# ADC.net
KiCad netlist of a schematic drawn in Altium Designer
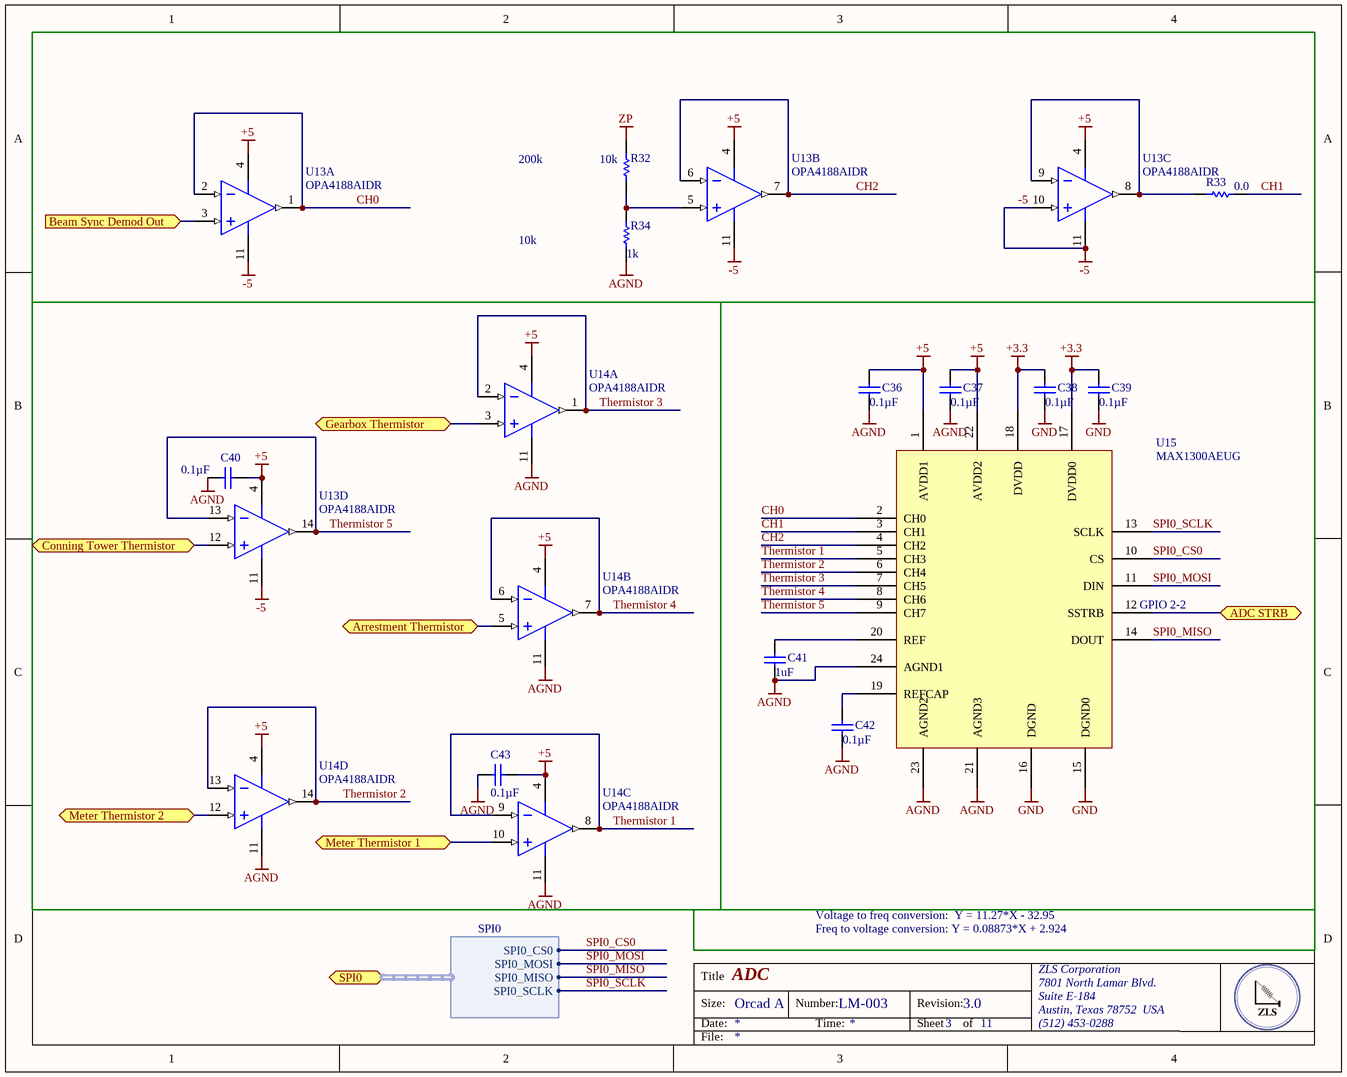
[diagram p0: ADC.SchDoc]

(export (version "E")
  (design (tool "Eeschema 10.0.6"))
  (components
    (comp (ref "C36")
      (value "CAP CER 0.1UF 25V X7R 0805")
      (footprint "CAPC0805(2012)145_N")
      (fields
        (field (name "MANUFACTURER") "Murata Electronics North America")
        (field (name "MANUFACTURER PART NUMBER") "GRM21BR71E104KA01L")
        (field (name "CAPACITANCE") "0.1µF")
        (field (name "TOLERANCE") "±10%")
      )
      (libsource (lib "Altium Content Vault") (part "CMP-1036-04795-1"))
    )
    (comp (ref "C37")
      (value "CAP CER 0.1UF 25V X7R 0805")
      (footprint "CAPC0805(2012)145_N")
      (fields
        (field (name "MANUFACTURER") "Murata Electronics North America")
        (field (name "MANUFACTURER PART NUMBER") "GRM21BR71E104KA01L")
        (field (name "CAPACITANCE") "0.1µF")
        (field (name "TOLERANCE") "±10%")
      )
      (libsource (lib "Altium Content Vault") (part "CMP-1036-04795-1"))
    )
    (comp (ref "C38")
      (value "CAP CER 0.1UF 25V X7R 0805")
      (footprint "CAPC0805(2012)145_N")
      (fields
        (field (name "MANUFACTURER") "Murata Electronics North America")
        (field (name "MANUFACTURER PART NUMBER") "GRM21BR71E104KA01L")
        (field (name "CAPACITANCE") "0.1µF")
        (field (name "TOLERANCE") "±10%")
      )
      (libsource (lib "Altium Content Vault") (part "CMP-1036-04795-1"))
    )
    (comp (ref "C39")
      (value "CAP CER 0.1UF 25V X7R 0805")
      (footprint "CAPC0805(2012)145_N")
      (fields
        (field (name "MANUFACTURER") "Murata Electronics North America")
        (field (name "MANUFACTURER PART NUMBER") "GRM21BR71E104KA01L")
        (field (name "CAPACITANCE") "0.1µF")
        (field (name "TOLERANCE") "±10%")
      )
      (libsource (lib "Altium Content Vault") (part "CMP-1036-04795-1"))
    )
    (comp (ref "C40")
      (value "CAP CER 0.1UF 16V X7R 0805")
      (footprint "CAPC0805(2012)145_N")
      (fields
        (field (name "TOLERANCE") "±10%")
        (field (name "MANUFACTURER") "Murata Electronics North America")
        (field (name "MANUFACTURER PART NUMBER") "GRM219R71C104KA01D")
        (field (name "CAPACITANCE") "0.1µF")
      )
      (libsource (lib "Altium Content Vault") (part "CMP-1036-04795-1"))
    )
    (comp (ref "C41")
      (value "CAP CER 1UF 16V X7R 0805")
      (footprint "CAPC0805(2012)145_N")
      (fields
        (field (name "MANUFACTURER") "Kemet")
        (field (name "MANUFACTURER PART NUMBER") "C0805X105K4RACTU")
        (field (name "CAPACITANCE") "1uF")
        (field (name "TOLERANCE") "10%")
      )
      (libsource (lib "Altium Content Vault") (part "CMP-1036-04795-1"))
    )
    (comp (ref "C42")
      (value "CAP CER 0.1UF 16V X7R 0805")
      (footprint "CAPC0805(2012)145_N")
      (fields
        (field (name "TOLERANCE") "±10%")
        (field (name "MANUFACTURER") "Murata Electronics North America")
        (field (name "MANUFACTURER PART NUMBER") "GRM219R71C104KA01D")
        (field (name "CAPACITANCE") "0.1µF")
      )
      (libsource (lib "Altium Content Vault") (part "CMP-1036-04795-1"))
    )
    (comp (ref "C43")
      (value "CAP CER 0.1UF 16V X7R 0805")
      (footprint "CAPC0805(2012)145_N")
      (fields
        (field (name "TOLERANCE") "±10%")
        (field (name "MANUFACTURER") "Murata Electronics North America")
        (field (name "MANUFACTURER PART NUMBER") "GRM219R71C104KA01D")
        (field (name "CAPACITANCE") "0.1µF")
      )
      (libsource (lib "Altium Content Vault") (part "CMP-1036-04795-1"))
    )
    (comp (ref "R32")
      (value "RES SMD 10K OHM 1% 1/8W 0805")
      (footprint "RESC0805(2012)_M")
      (fields
        (field (name "MANUFACTURER") "Vishay Dale")
        (field (name "MANUFACTURER PART NUMBER") "CRCW080510K0FKTA")
        (field (name "RESISTANCE (OHMS)") "10k")
        (field (name "TOLERANCE") "±1%")
      )
      (libsource (lib "Altium Content Vault") (part "CMP-1013-00017-1"))
    )
    (comp (ref "R33")
      (value "RES SMD 0.0 OHM JUMPER 1/8W 0805")
      (footprint "RESC0805(2012)_M")
      (fields
        (field (name "MANUFACTURER") "Vishay Dale")
        (field (name "MANUFACTURER PART NUMBER") "CRCW08050000Z0EA")
        (field (name "RESISTANCE (OHMS)") "0.0")
        (field (name "TOLERANCE") "Jumper")
      )
      (libsource (lib "Altium Content Vault") (part "CMP-1013-00017-1"))
    )
    (comp (ref "R34")
      (value "RES SMD 1K OHM 1% 1/8W 0805")
      (footprint "RESC0805(2012)_M")
      (fields
        (field (name "MANUFACTURER") "Vishay Dale")
        (field (name "MANUFACTURER PART NUMBER") "CRCW08051K00FKTA")
        (field (name "RESISTANCE (OHMS)") "1k")
        (field (name "TOLERANCE") "±1%")
      )
      (libsource (lib "Altium Content Vault") (part "CMP-1013-00017-1"))
    )
    (comp (ref "U13")
      (value "OPA4188AIDR")
      (footprint "D0014A_L")
      (fields (field (name "MANUFACTURER") "Texas Instruments"))
      (libsource (lib "Altium Content Vault") (part "TI-OPA4188-D14"))
    )
    (comp (ref "U14")
      (value "OPA4188AIDR")
      (footprint "D0014A_L")
      (fields (field (name "MANUFACTURER") "Texas Instruments"))
      (libsource (lib "Altium Content Vault") (part "TI-OPA4188-D14"))
    )
    (comp (ref "U15")
      (value "MAX1300AEUG")
      (footprint "TSOP65P640X90-24N")
      (description "IC ADC 16BIT SRL 115KSPS 24TSSOP")
      (libsource (lib "ZLS_LIB") (part "MAX1300AEUG"))
    )
  )
  (nets
    (net (code "2") (name "+3.3") (class "Default")
      (node (ref "C38") (pin "1") (pinfunction "1_1") (pintype "passive"))
      (node (ref "C39") (pin "1") (pinfunction "1_1") (pintype "passive"))
      (node (ref "U15") (pin "17") (pinfunction "DVDD0_17") (pintype "passive"))
      (node (ref "U15") (pin "18") (pinfunction "DVDD_18") (pintype "passive"))
    )
    (net (code "3") (name "+5") (class "Default")
      (node (ref "C36") (pin "1") (pinfunction "1_1") (pintype "passive"))
      (node (ref "C37") (pin "1") (pinfunction "1_1") (pintype "passive"))
      (node (ref "C40") (pin "2") (pinfunction "2_2") (pintype "passive"))
      (node (ref "C43") (pin "2") (pinfunction "2_2") (pintype "passive"))
      (node (ref "U13") (pin "4") (pinfunction "V+_4") (pintype "power_in"))
      (node (ref "U14") (pin "4") (pinfunction "V+_4") (pintype "power_in"))
      (node (ref "U15") (pin "1") (pinfunction "AVDD1_1") (pintype "passive"))
      (node (ref "U15") (pin "22") (pinfunction "AVDD2_22") (pintype "passive"))
    )
    (net (code "4") (name "-5") (class "Default")
      (node (ref "U13") (pin "10") (pinfunction "IN_C+_10") (pintype "input"))
      (node (ref "U13") (pin "11") (pinfunction "V-_11") (pintype "power_in"))
    )
    (net (code "5") (name "/ADC STRB") (class "Default")
      (node (ref "U15") (pin "12") (pinfunction "SSTRB_12") (pintype "passive"))
    )
    (net (code "6") (name "/Arrestment Thermistor") (class "Default")
      (node (ref "U14") (pin "5") (pinfunction "IN_B+_5") (pintype "input"))
    )
    (net (code "7") (name "/Beam Sync Demod Out") (class "Default")
      (node (ref "U13") (pin "3") (pinfunction "IN_A+_3") (pintype "input"))
    )
    (net (code "8") (name "/CH0") (class "Default")
      (node (ref "U13") (pin "1") (pinfunction "OUT_A_1") (pintype "output"))
      (node (ref "U13") (pin "2") (pinfunction "IN_A-_2") (pintype "input"))
      (node (ref "U15") (pin "2") (pinfunction "CH0_2") (pintype "passive"))
    )
    (net (code "9") (name "/CH1") (class "Default")
      (node (ref "R33") (pin "1") (pinfunction "1_1") (pintype "passive"))
      (node (ref "U15") (pin "3") (pinfunction "CH1_3") (pintype "passive"))
    )
    (net (code "10") (name "/CH2") (class "Default")
      (node (ref "U13") (pin "6") (pinfunction "IN_B-_6") (pintype "input"))
      (node (ref "U13") (pin "7") (pinfunction "OUT_B_7") (pintype "output"))
      (node (ref "U15") (pin "4") (pinfunction "CH2_4") (pintype "passive"))
    )
    (net (code "11") (name "/Conning Tower Thermistor") (class "Default")
      (node (ref "U13") (pin "12") (pinfunction "IN_D+_12") (pintype "input"))
    )
    (net (code "12") (name "/Gearbox Thermistor") (class "Default")
      (node (ref "U14") (pin "3") (pinfunction "IN_A+_3") (pintype "input"))
    )
    (net (code "13") (name "/Meter Thermistor 1") (class "Default")
      (node (ref "U14") (pin "10") (pinfunction "IN_C+_10") (pintype "input"))
    )
    (net (code "14") (name "/Meter Thermistor 2") (class "Default")
      (node (ref "U14") (pin "12") (pinfunction "IN_D+_12") (pintype "input"))
    )
    (net (code "15") (name "/SPI0_CS0") (class "Default")
      (node (ref "U15") (pin "10") (pinfunction "CS_10") (pintype "passive"))
    )
    (net (code "16") (name "/SPI0_MISO") (class "Default")
      (node (ref "U15") (pin "14") (pinfunction "DOUT_14") (pintype "passive"))
    )
    (net (code "17") (name "/SPI0_MOSI") (class "Default")
      (node (ref "U15") (pin "11") (pinfunction "DIN_11") (pintype "passive"))
    )
    (net (code "18") (name "/SPI0_SCLK") (class "Default")
      (node (ref "U15") (pin "13") (pinfunction "SCLK_13") (pintype "passive"))
    )
    (net (code "19") (name "/Thermistor 1") (class "Default")
      (node (ref "U14") (pin "8") (pinfunction "OUT_C_8") (pintype "output"))
      (node (ref "U14") (pin "9") (pinfunction "IN_C-_9") (pintype "input"))
      (node (ref "U15") (pin "5") (pinfunction "CH3_5") (pintype "passive"))
    )
    (net (code "20") (name "/Thermistor 2") (class "Default")
      (node (ref "U14") (pin "13") (pinfunction "IN_D-_13") (pintype "input"))
      (node (ref "U14") (pin "14") (pinfunction "OUT_D_14") (pintype "output"))
      (node (ref "U15") (pin "6") (pinfunction "CH4_6") (pintype "passive"))
    )
    (net (code "21") (name "/Thermistor 3") (class "Default")
      (node (ref "U14") (pin "1") (pinfunction "OUT_A_1") (pintype "output"))
      (node (ref "U14") (pin "2") (pinfunction "IN_A-_2") (pintype "input"))
      (node (ref "U15") (pin "7") (pinfunction "CH5_7") (pintype "passive"))
    )
    (net (code "22") (name "/Thermistor 4") (class "Default")
      (node (ref "U14") (pin "6") (pinfunction "IN_B-_6") (pintype "input"))
      (node (ref "U14") (pin "7") (pinfunction "OUT_B_7") (pintype "output"))
      (node (ref "U15") (pin "8") (pinfunction "CH6_8") (pintype "passive"))
    )
    (net (code "23") (name "/Thermistor 5") (class "Default")
      (node (ref "U13") (pin "13") (pinfunction "IN_D-_13") (pintype "input"))
      (node (ref "U13") (pin "14") (pinfunction "OUT_D_14") (pintype "output"))
      (node (ref "U15") (pin "9") (pinfunction "CH7_9") (pintype "passive"))
    )
    (net (code "25") (name "AGND") (class "Default")
      (node (ref "C36") (pin "2") (pinfunction "2_2") (pintype "passive"))
      (node (ref "C37") (pin "2") (pinfunction "2_2") (pintype "passive"))
      (node (ref "C40") (pin "1") (pinfunction "1_1") (pintype "passive"))
      (node (ref "C41") (pin "2") (pinfunction "2_2") (pintype "passive"))
      (node (ref "C42") (pin "2") (pinfunction "2_2") (pintype "passive"))
      (node (ref "C43") (pin "1") (pinfunction "1_1") (pintype "passive"))
      (node (ref "R34") (pin "1") (pinfunction "1_1") (pintype "passive"))
      (node (ref "U14") (pin "11") (pinfunction "V-_11") (pintype "power_in"))
      (node (ref "U15") (pin "21") (pinfunction "AGND3_21") (pintype "passive"))
      (node (ref "U15") (pin "23") (pinfunction "AGND2_23") (pintype "passive"))
      (node (ref "U15") (pin "24") (pinfunction "AGND1_24") (pintype "passive"))
    )
    (net (code "26") (name "GND") (class "Default")
      (node (ref "C38") (pin "2") (pinfunction "2_2") (pintype "passive"))
      (node (ref "C39") (pin "2") (pinfunction "2_2") (pintype "passive"))
      (node (ref "U15") (pin "15") (pinfunction "DGND0_15") (pintype "passive"))
      (node (ref "U15") (pin "16") (pinfunction "DGND_16") (pintype "passive"))
    )
    (net (code "27") (name "Net-(U13B-IN_B+)") (class "Default")
      (node (ref "R32") (pin "1") (pinfunction "1_1") (pintype "passive"))
      (node (ref "R34") (pin "2") (pinfunction "2_2") (pintype "passive"))
      (node (ref "U13") (pin "5") (pinfunction "IN_B+_5") (pintype "input"))
    )
    (net (code "28") (name "Net-(U13C-IN_C-)") (class "Default")
      (node (ref "R33") (pin "2") (pinfunction "2_2") (pintype "passive"))
      (node (ref "U13") (pin "8") (pinfunction "OUT_C_8") (pintype "output"))
      (node (ref "U13") (pin "9") (pinfunction "IN_C-_9") (pintype "input"))
    )
    (net (code "29") (name "Net-(U15-REF)") (class "Default")
      (node (ref "C41") (pin "1") (pinfunction "1_1") (pintype "passive"))
      (node (ref "U15") (pin "20") (pinfunction "REF_20") (pintype "passive"))
    )
    (net (code "30") (name "Net-(U15-REFCAP)") (class "Default")
      (node (ref "C42") (pin "1") (pinfunction "1_1") (pintype "passive"))
      (node (ref "U15") (pin "19") (pinfunction "REFCAP_19") (pintype "passive"))
    )
    (net (code "31") (name "ZP") (class "Default")
      (node (ref "R32") (pin "2") (pinfunction "2_2") (pintype "passive"))
    )
  )
)
